# SCH_FMC-R2_MTOP_2026-02-22.net
KiCad netlist of a schematic drawn in EasyEDA
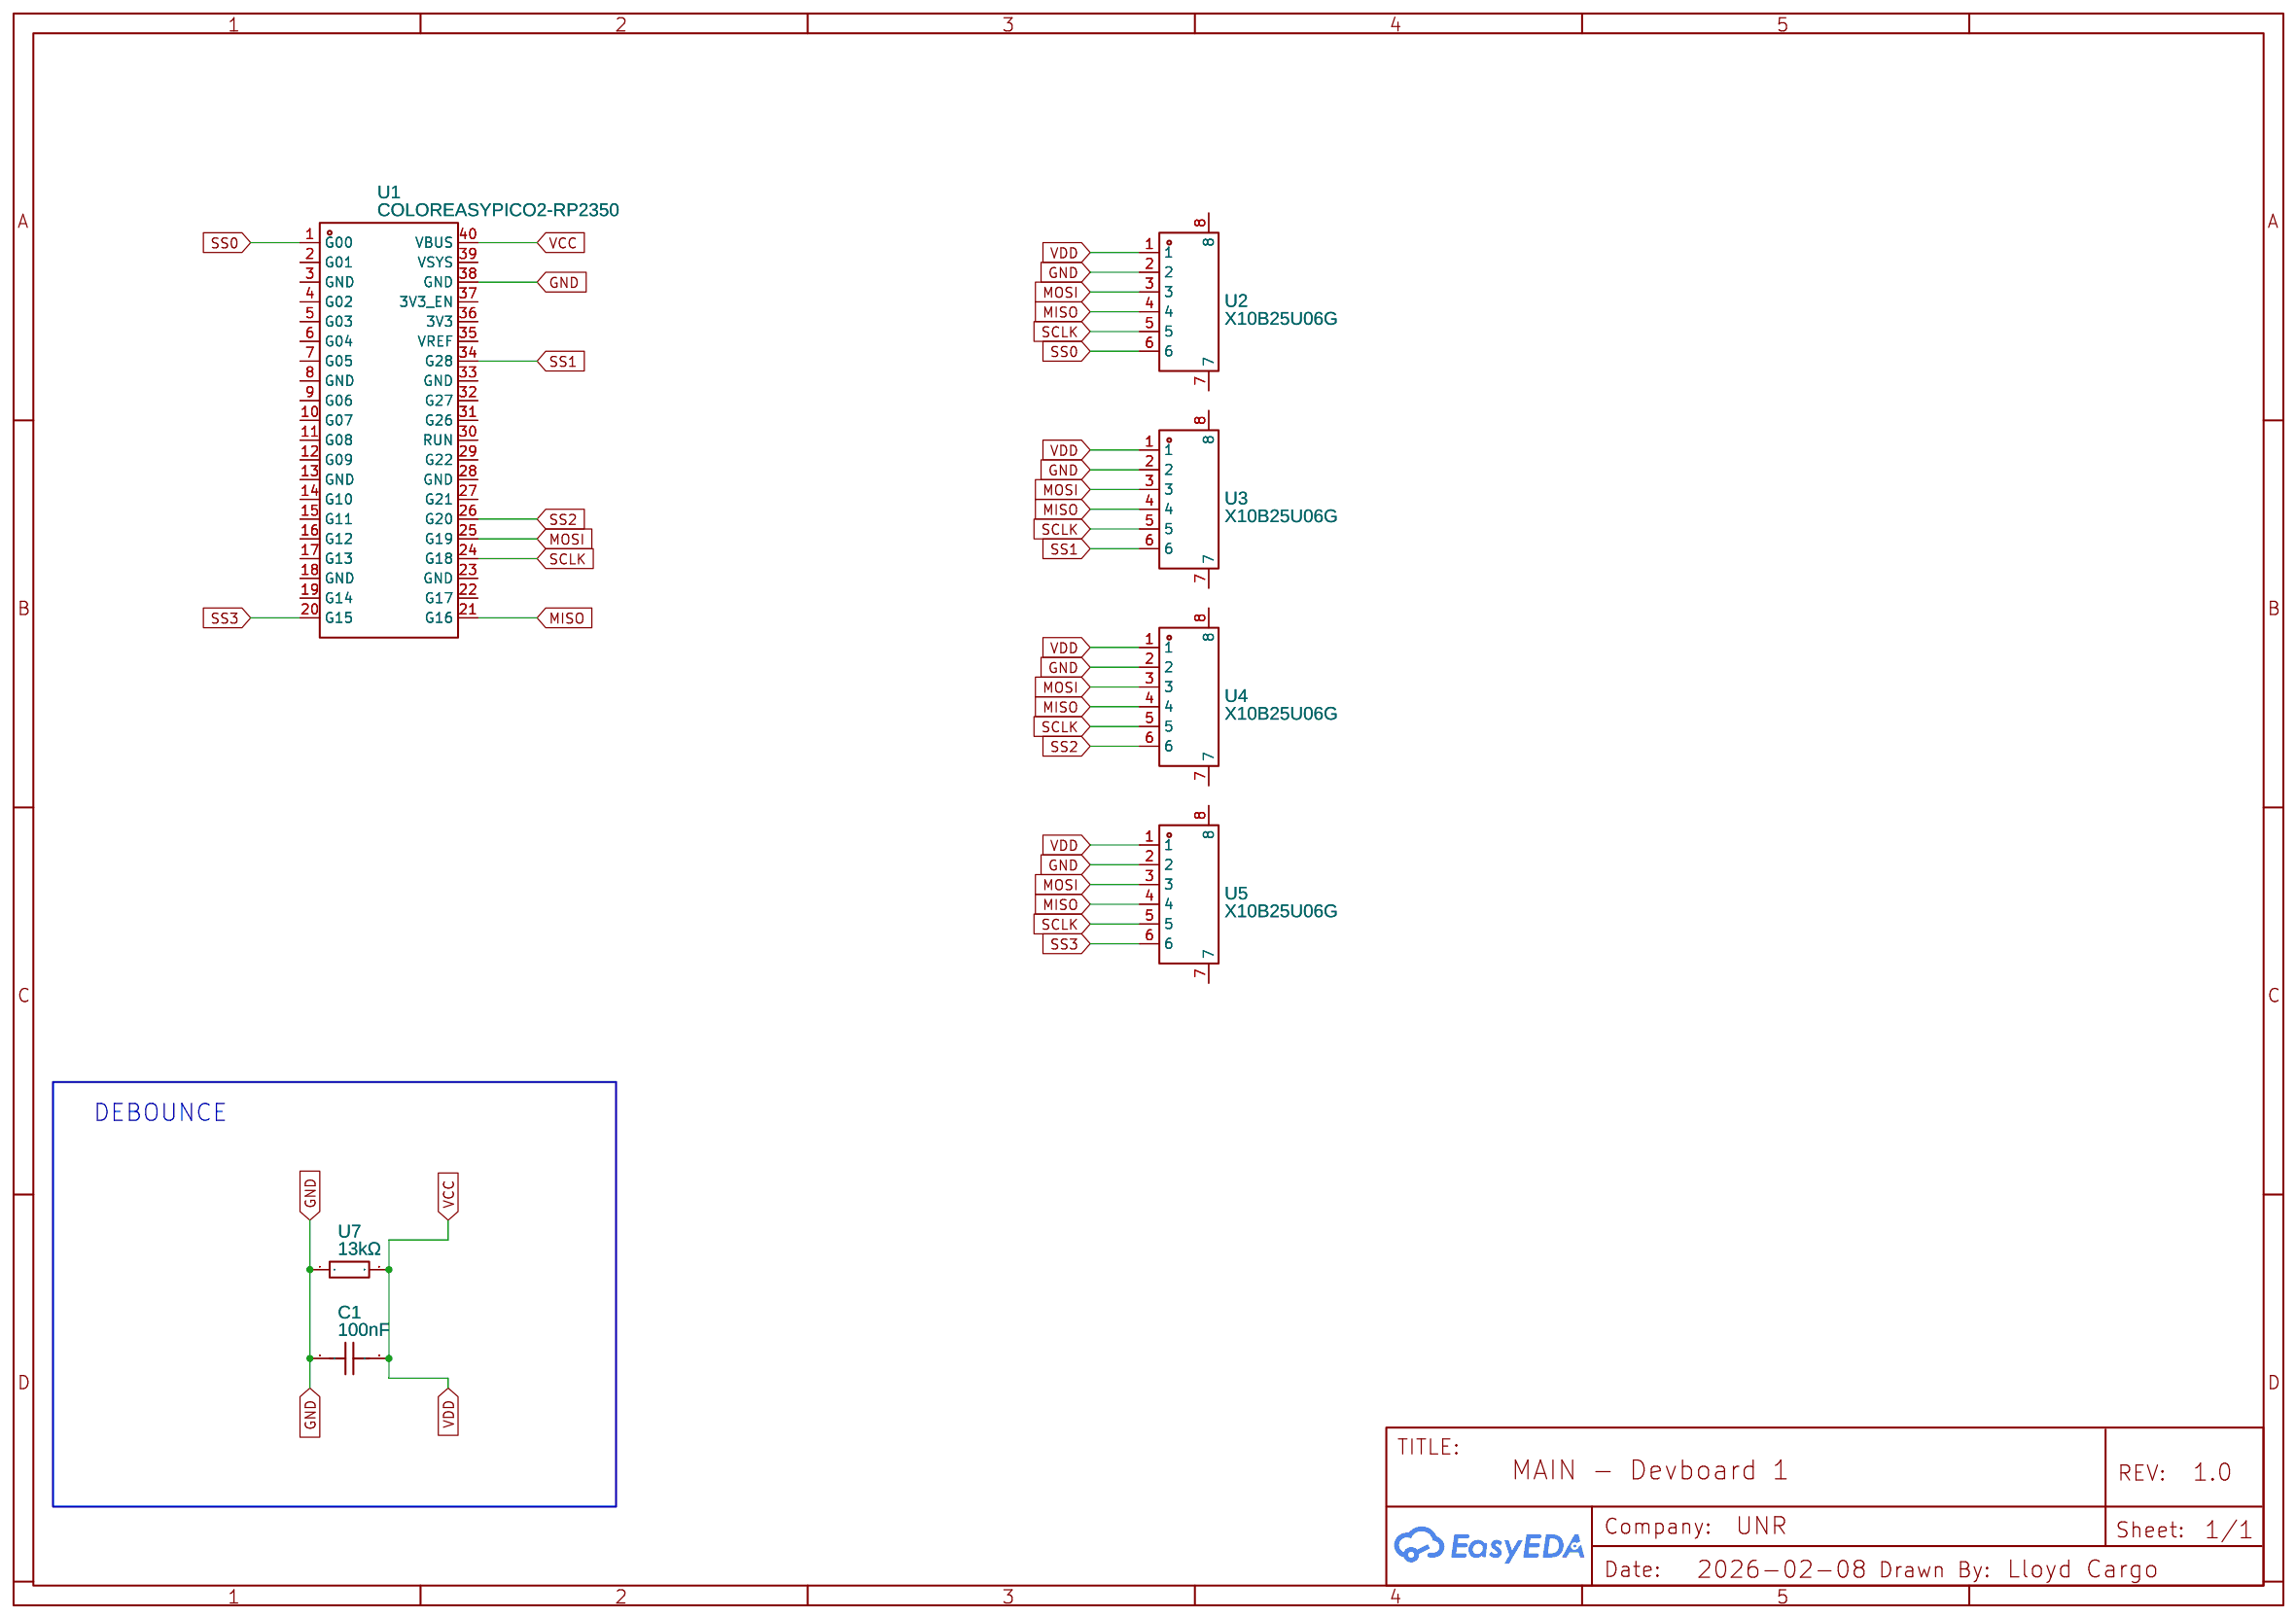
[diagram p0: MAIN]
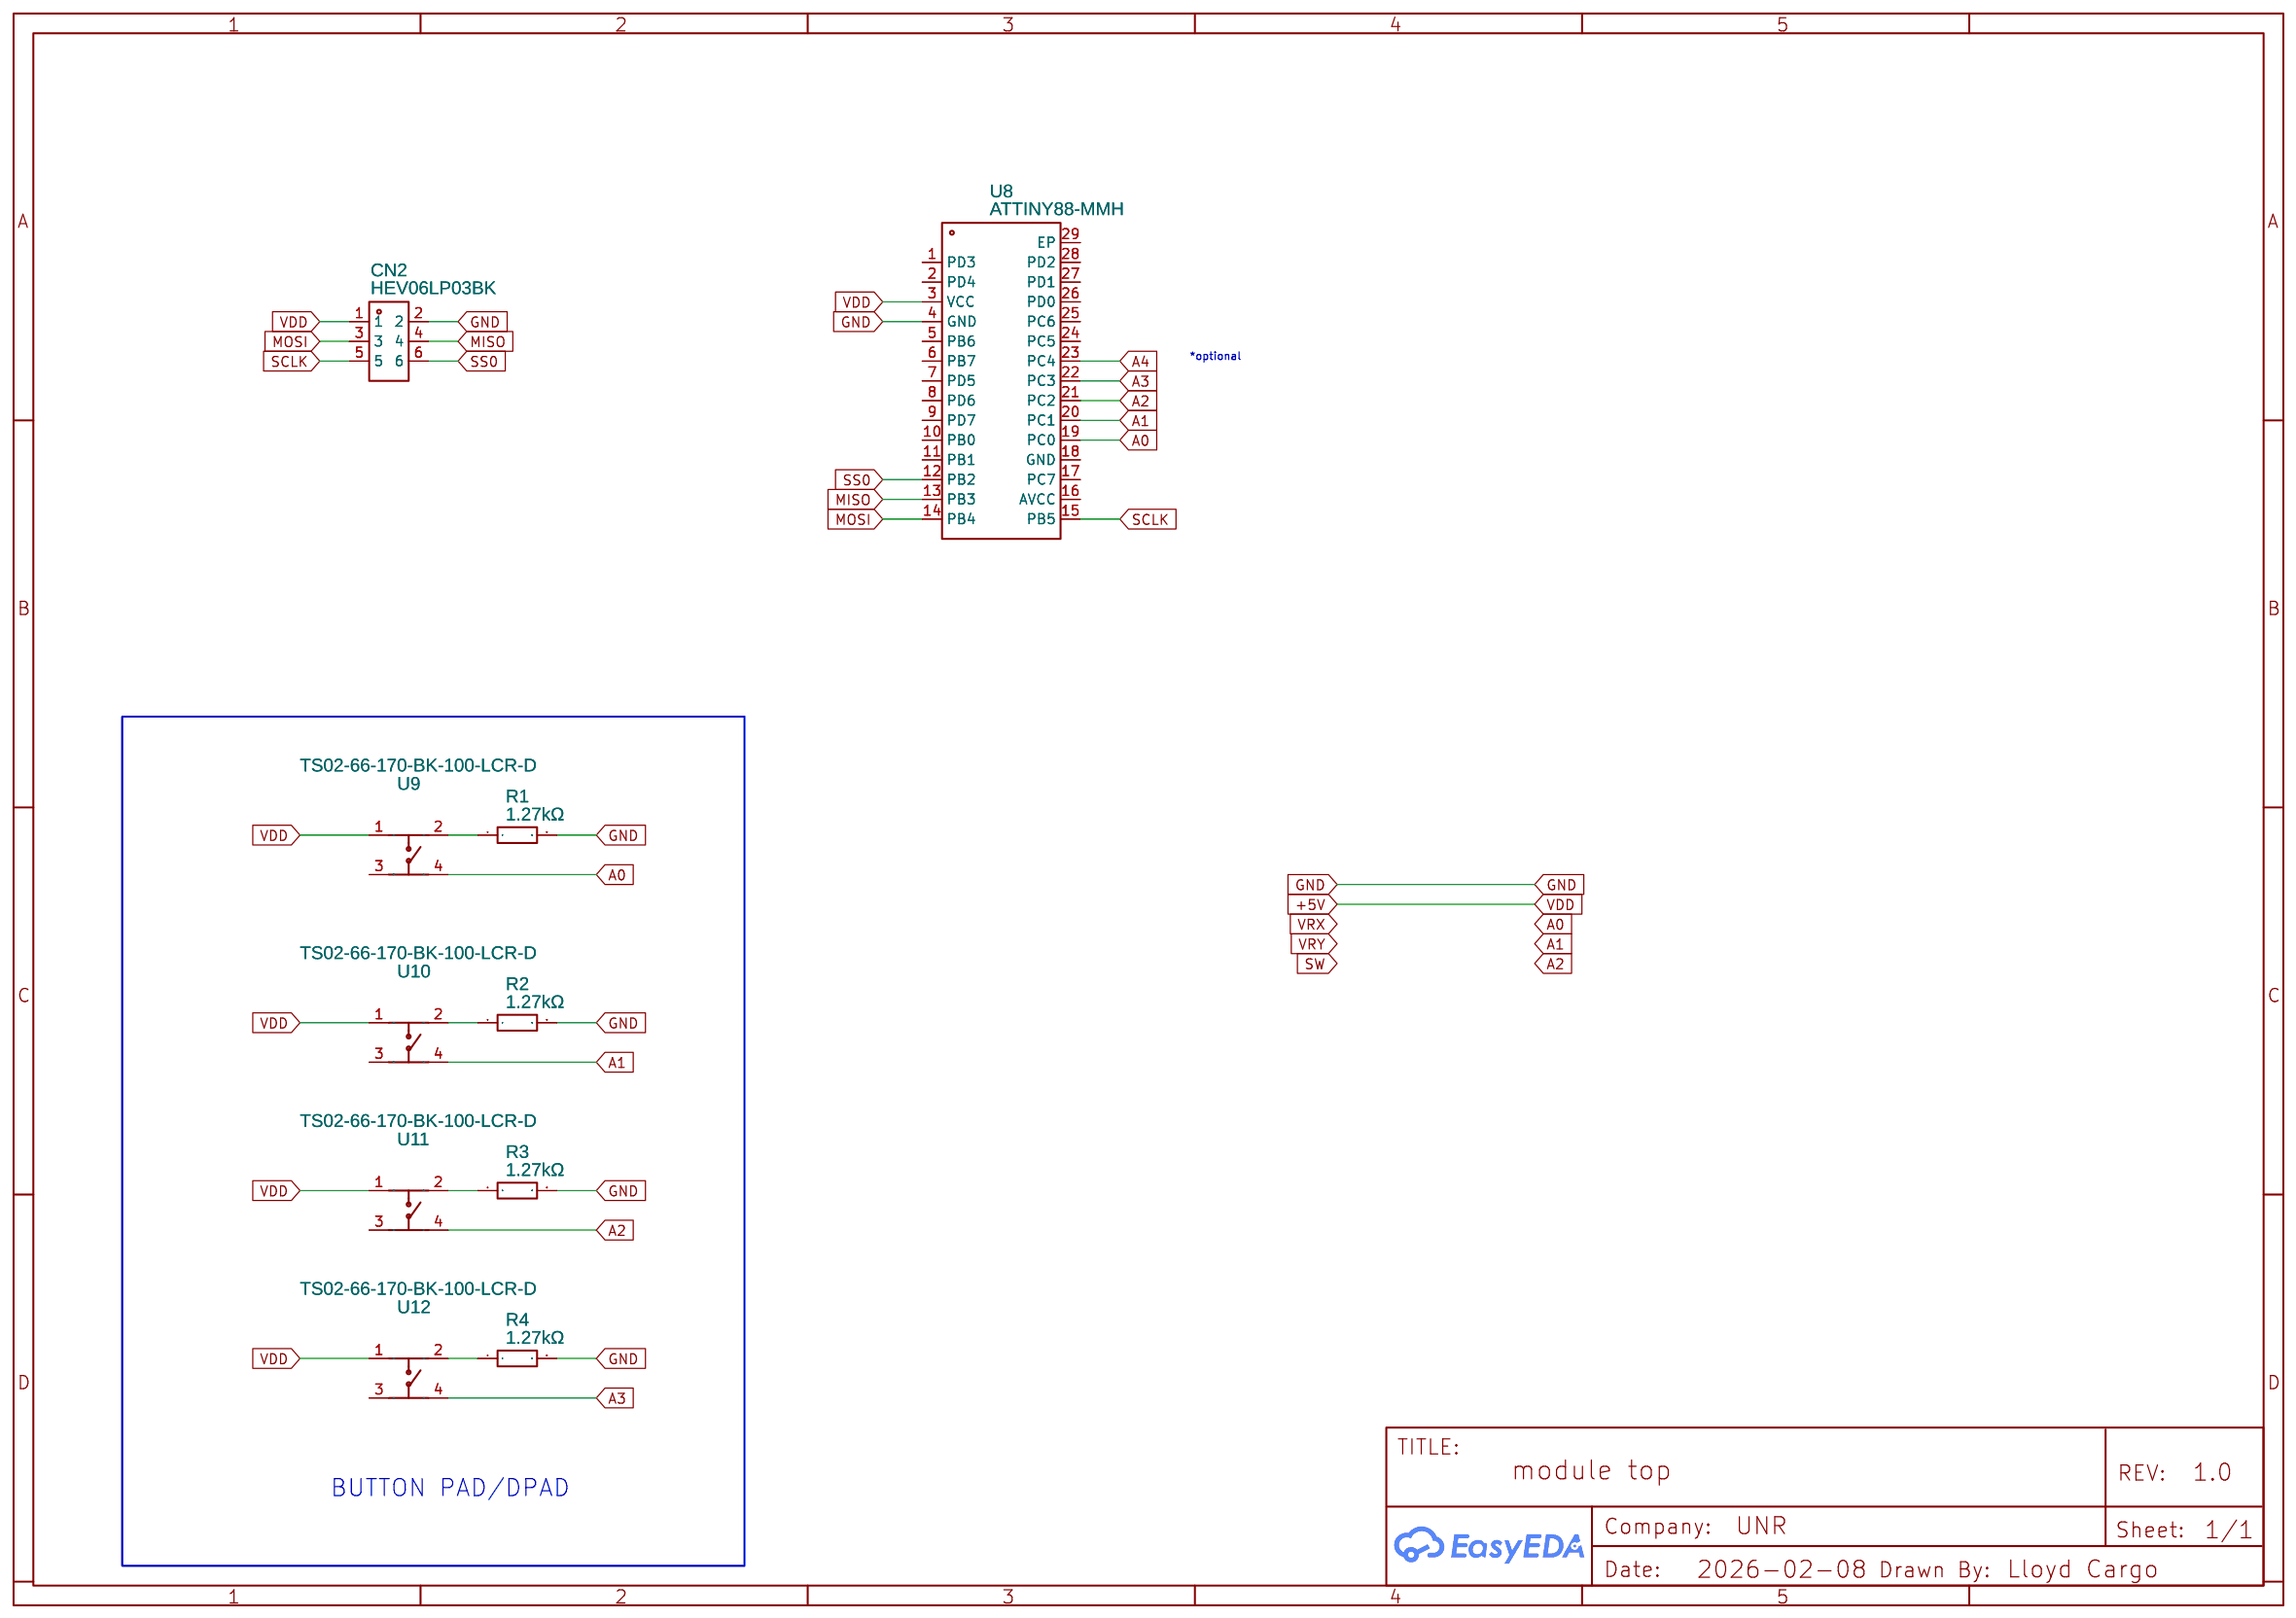
[diagram p1: module top]
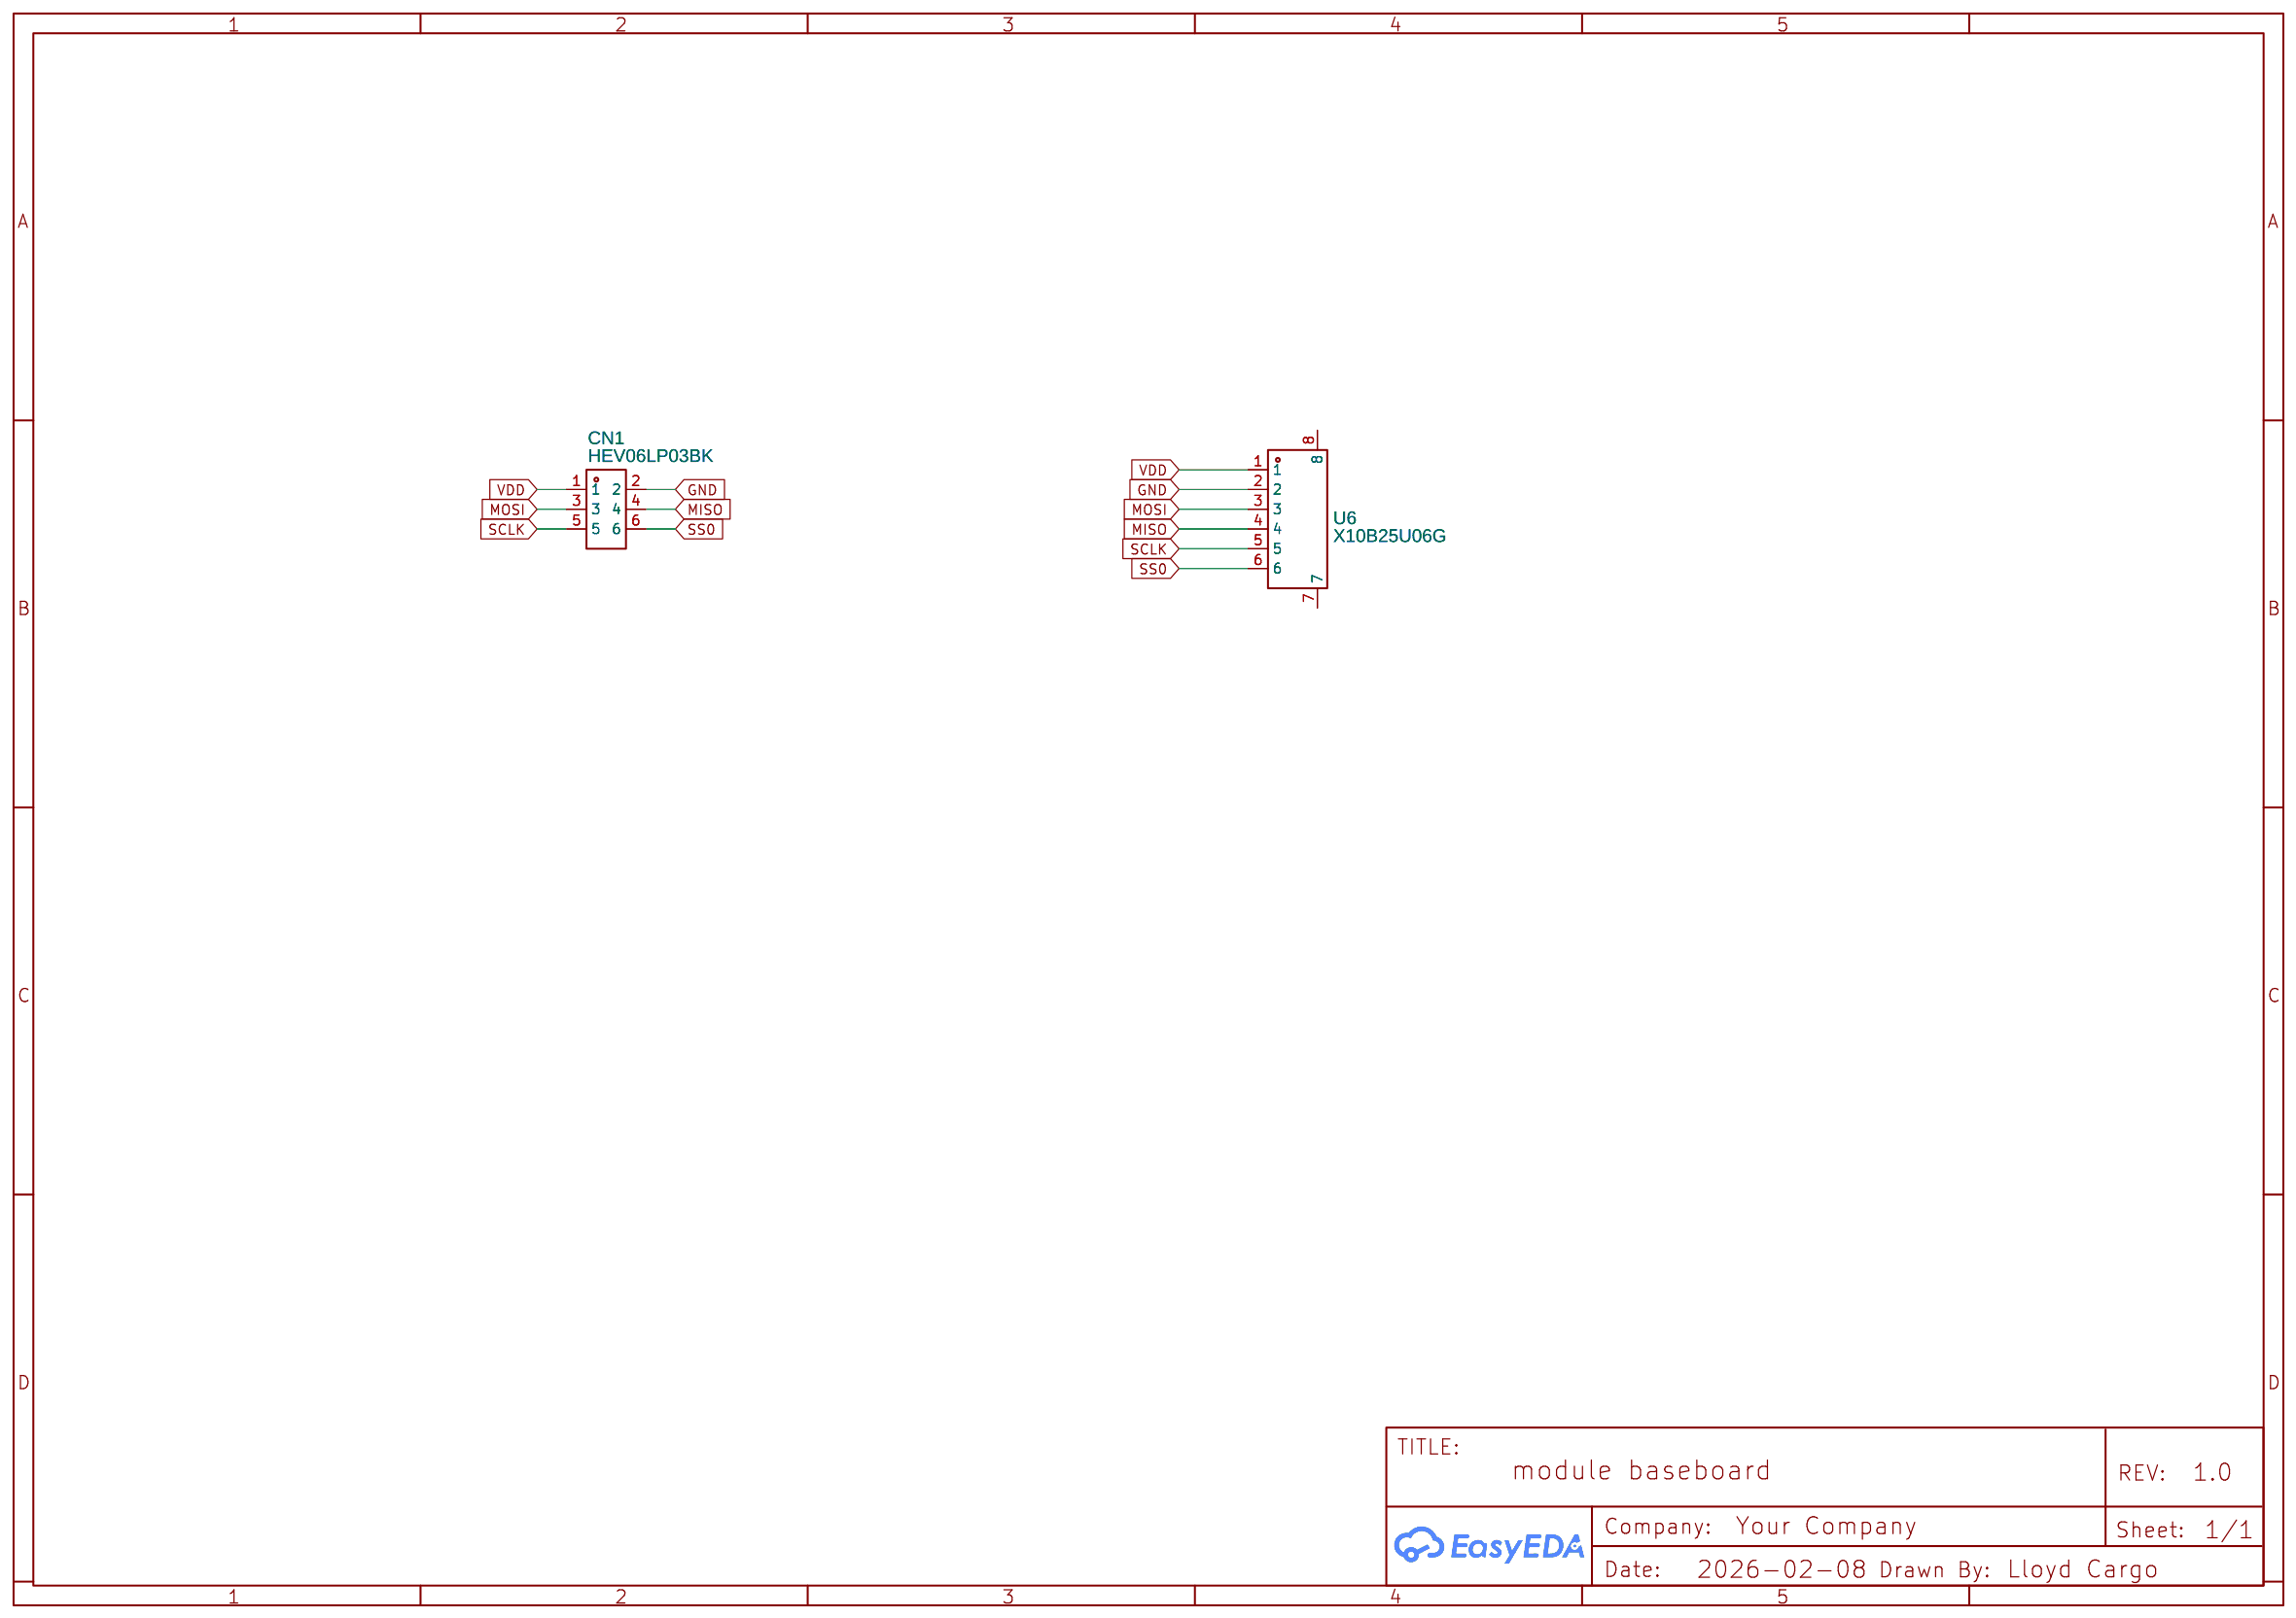
[diagram p2: module baseboard]

(export (version "E")
  (design (tool "Eeschema 10.0.6"))
  (components
    (comp (ref "C1")
      (value "100nF")
      (fields
        (field (name "Manufacturer Part") "GCG188R92A104KA03D")
        (field (name "Manufacturer") "muRata(村田)")
      )
      (libsource (lib "") (part "GCG188R92A104KA03D"))
    )
    (comp (ref "U1")
      (value "COLOREASYPICO2-RP2350")
      (fields
        (field (name "Manufacturer Part") "ColorEasyPico2-RP2350")
        (field (name "Manufacturer") "立创开发板")
      )
      (libsource (lib "") (part "COLOREASYPICO2-RP2350"))
    )
    (comp (ref "U2")
      (value "X10B25U06G")
      (fields (field (name "Manufacturer") "XKB Connection(中国星坤)"))
      (libsource (lib "") (part "X10B25U06G"))
    )
    (comp (ref "U3")
      (value "X10B25U06G")
      (fields (field (name "Manufacturer") "XKB Connection(中国星坤)"))
      (libsource (lib "") (part "X10B25U06G"))
    )
    (comp (ref "U4")
      (value "X10B25U06G")
      (fields (field (name "Manufacturer") "XKB Connection(中国星坤)"))
      (libsource (lib "") (part "X10B25U06G"))
    )
    (comp (ref "U5")
      (value "X10B25U06G")
      (fields (field (name "Manufacturer") "XKB Connection(中国星坤)"))
      (libsource (lib "") (part "X10B25U06G"))
    )
    (comp (ref "U7")
      (value "13kΩ")
      (fields (field (name "Manufacturer Part") "HPCR0805F13K0K9") (field (name "Manufacturer") "RESI(开步睿思)"))
      (libsource (lib "") (part "HPCR0805F13K0K9"))
    )
    (comp (ref "CN2")
      (value "HEV06LP03BK")
      (fields (field (name "Manufacturer") "WingTAT(格林柏)"))
      (libsource (lib "") (part "HEV06LP03BK"))
    )
    (comp (ref "R1")
      (value "1.27kΩ")
      (fields (field (name "Manufacturer Part") "RC0603FR-071K27L") (field (name "Manufacturer") "YAGEO(国巨)"))
      (libsource (lib "") (part "RC0603FR-071K27L"))
    )
    (comp (ref "R2")
      (value "1.27kΩ")
      (fields (field (name "Manufacturer Part") "RC0603FR-071K27L") (field (name "Manufacturer") "YAGEO(国巨)"))
      (libsource (lib "") (part "RC0603FR-071K27L"))
    )
    (comp (ref "R3")
      (value "1.27kΩ")
      (fields (field (name "Manufacturer Part") "RC0603FR-071K27L") (field (name "Manufacturer") "YAGEO(国巨)"))
      (libsource (lib "") (part "RC0603FR-071K27L"))
    )
    (comp (ref "R4")
      (value "1.27kΩ")
      (fields (field (name "Manufacturer Part") "RC0603FR-071K27L") (field (name "Manufacturer") "YAGEO(国巨)"))
      (libsource (lib "") (part "RC0603FR-071K27L"))
    )
    (comp (ref "U8")
      (value "ATTINY88-MMH")
      (fields (field (name "Manufacturer") "MICROCHIP(美国微芯)"))
      (libsource (lib "") (part "ATTINY88-MMH"))
    )
    (comp (ref "U9")
      (value "TS02-66-170-BK-100-LCR-D")
      (fields (field (name "Manufacturer") "CUI"))
      (libsource (lib "") (part "TS02-66-170-BK-100-LCR-D"))
    )
    (comp (ref "U10")
      (value "TS02-66-170-BK-100-LCR-D")
      (fields (field (name "Manufacturer") "CUI"))
      (libsource (lib "") (part "TS02-66-170-BK-100-LCR-D"))
    )
    (comp (ref "U11")
      (value "TS02-66-170-BK-100-LCR-D")
      (fields (field (name "Manufacturer") "CUI"))
      (libsource (lib "") (part "TS02-66-170-BK-100-LCR-D"))
    )
    (comp (ref "U12")
      (value "TS02-66-170-BK-100-LCR-D")
      (fields (field (name "Manufacturer") "CUI"))
      (libsource (lib "") (part "TS02-66-170-BK-100-LCR-D"))
    )
    (comp (ref "CN1")
      (value "HEV06LP03BK")
      (fields (field (name "Manufacturer") "WingTAT(格林柏)"))
      (libsource (lib "") (part "HEV06LP03BK"))
    )
    (comp (ref "U6")
      (value "X10B25U06G")
      (fields (field (name "Manufacturer") "XKB Connection(中国星坤)"))
      (libsource (lib "") (part "X10B25U06G"))
    )
  )
  (nets
    (net (code "1") (name "+5V") (class "Default")
      (node (ref "C1") (pin "2") (pinfunction "2_2") (pintype "unspecified"))
      (node (ref "CN1") (pin "1") (pinfunction "1_1") (pintype "unspecified"))
      (node (ref "CN2") (pin "1") (pinfunction "1_1") (pintype "unspecified"))
      (node (ref "U1") (pin "40") (pinfunction "VBUS_40") (pintype "unspecified"))
      (node (ref "U10") (pin "1") (pinfunction "1_1") (pintype "unspecified"))
      (node (ref "U11") (pin "1") (pinfunction "1_1") (pintype "unspecified"))
      (node (ref "U12") (pin "1") (pinfunction "1_1") (pintype "unspecified"))
      (node (ref "U2") (pin "1") (pinfunction "1_1") (pintype "unspecified"))
      (node (ref "U3") (pin "1") (pinfunction "1_1") (pintype "unspecified"))
      (node (ref "U4") (pin "1") (pinfunction "1_1") (pintype "unspecified"))
      (node (ref "U5") (pin "1") (pinfunction "1_1") (pintype "unspecified"))
      (node (ref "U6") (pin "1") (pinfunction "1_1") (pintype "unspecified"))
      (node (ref "U7") (pin "2") (pinfunction "2_2") (pintype "unspecified"))
      (node (ref "U8") (pin "3") (pinfunction "VCC_3") (pintype "unspecified"))
      (node (ref "U9") (pin "1") (pinfunction "1_1") (pintype "unspecified"))
    )
    (net (code "2") (name "A0") (class "Default")
      (node (ref "U8") (pin "19") (pinfunction "PC0_19") (pintype "unspecified"))
      (node (ref "U9") (pin "4") (pinfunction "4_4") (pintype "unspecified"))
    )
    (net (code "3") (name "A1") (class "Default")
      (node (ref "U10") (pin "4") (pinfunction "4_4") (pintype "unspecified"))
      (node (ref "U8") (pin "20") (pinfunction "PC1_20") (pintype "unspecified"))
    )
    (net (code "4") (name "A2") (class "Default")
      (node (ref "U11") (pin "4") (pinfunction "4_4") (pintype "unspecified"))
      (node (ref "U8") (pin "21") (pinfunction "PC2_21") (pintype "unspecified"))
    )
    (net (code "5") (name "A3") (class "Default")
      (node (ref "U12") (pin "4") (pinfunction "4_4") (pintype "unspecified"))
      (node (ref "U8") (pin "22") (pinfunction "PC3_22") (pintype "unspecified"))
    )
    (net (code "6") (name "A4") (class "Default")
      (node (ref "U8") (pin "23") (pinfunction "PC4_23") (pintype "unspecified"))
    )
    (net (code "7") (name "GND") (class "Default")
      (node (ref "C1") (pin "1") (pinfunction "1_1") (pintype "unspecified"))
      (node (ref "CN1") (pin "2") (pinfunction "2_2") (pintype "unspecified"))
      (node (ref "CN2") (pin "2") (pinfunction "2_2") (pintype "unspecified"))
      (node (ref "R1") (pin "2") (pinfunction "2_2") (pintype "unspecified"))
      (node (ref "R2") (pin "2") (pinfunction "2_2") (pintype "unspecified"))
      (node (ref "R3") (pin "2") (pinfunction "2_2") (pintype "unspecified"))
      (node (ref "R4") (pin "2") (pinfunction "2_2") (pintype "unspecified"))
      (node (ref "U1") (pin "38") (pinfunction "GND_38") (pintype "unspecified"))
      (node (ref "U2") (pin "2") (pinfunction "2_2") (pintype "unspecified"))
      (node (ref "U3") (pin "2") (pinfunction "2_2") (pintype "unspecified"))
      (node (ref "U4") (pin "2") (pinfunction "2_2") (pintype "unspecified"))
      (node (ref "U5") (pin "2") (pinfunction "2_2") (pintype "unspecified"))
      (node (ref "U6") (pin "2") (pinfunction "2_2") (pintype "unspecified"))
      (node (ref "U7") (pin "1") (pinfunction "1_1") (pintype "unspecified"))
      (node (ref "U8") (pin "4") (pinfunction "GND_4") (pintype "unspecified"))
    )
    (net (code "8") (name "MISO") (class "Default")
      (node (ref "CN1") (pin "4") (pinfunction "4_4") (pintype "unspecified"))
      (node (ref "CN2") (pin "4") (pinfunction "4_4") (pintype "unspecified"))
      (node (ref "U1") (pin "21") (pinfunction "G16_21") (pintype "unspecified"))
      (node (ref "U2") (pin "4") (pinfunction "4_4") (pintype "unspecified"))
      (node (ref "U3") (pin "4") (pinfunction "4_4") (pintype "unspecified"))
      (node (ref "U4") (pin "4") (pinfunction "4_4") (pintype "unspecified"))
      (node (ref "U5") (pin "4") (pinfunction "4_4") (pintype "unspecified"))
      (node (ref "U6") (pin "4") (pinfunction "4_4") (pintype "unspecified"))
      (node (ref "U8") (pin "13") (pinfunction "PB3_13") (pintype "unspecified"))
    )
    (net (code "9") (name "MOSI") (class "Default")
      (node (ref "CN1") (pin "3") (pinfunction "3_3") (pintype "unspecified"))
      (node (ref "CN2") (pin "3") (pinfunction "3_3") (pintype "unspecified"))
      (node (ref "U1") (pin "25") (pinfunction "G19_25") (pintype "unspecified"))
      (node (ref "U2") (pin "3") (pinfunction "3_3") (pintype "unspecified"))
      (node (ref "U3") (pin "3") (pinfunction "3_3") (pintype "unspecified"))
      (node (ref "U4") (pin "3") (pinfunction "3_3") (pintype "unspecified"))
      (node (ref "U5") (pin "3") (pinfunction "3_3") (pintype "unspecified"))
      (node (ref "U6") (pin "3") (pinfunction "3_3") (pintype "unspecified"))
      (node (ref "U8") (pin "14") (pinfunction "PB4_14") (pintype "unspecified"))
    )
    (net (code "10") (name "Net-(R1-Pad1)") (class "Default")
      (node (ref "R1") (pin "1") (pinfunction "1_1") (pintype "unspecified"))
      (node (ref "U9") (pin "2") (pinfunction "2_2") (pintype "unspecified"))
    )
    (net (code "11") (name "Net-(R2-Pad1)") (class "Default")
      (node (ref "R2") (pin "1") (pinfunction "1_1") (pintype "unspecified"))
      (node (ref "U10") (pin "2") (pinfunction "2_2") (pintype "unspecified"))
    )
    (net (code "12") (name "Net-(R3-Pad1)") (class "Default")
      (node (ref "R3") (pin "1") (pinfunction "1_1") (pintype "unspecified"))
      (node (ref "U11") (pin "2") (pinfunction "2_2") (pintype "unspecified"))
    )
    (net (code "13") (name "Net-(R4-Pad1)") (class "Default")
      (node (ref "R4") (pin "1") (pinfunction "1_1") (pintype "unspecified"))
      (node (ref "U12") (pin "2") (pinfunction "2_2") (pintype "unspecified"))
    )
    (net (code "14") (name "SCLK") (class "Default")
      (node (ref "CN1") (pin "5") (pinfunction "5_5") (pintype "unspecified"))
      (node (ref "CN2") (pin "5") (pinfunction "5_5") (pintype "unspecified"))
      (node (ref "U1") (pin "24") (pinfunction "G18_24") (pintype "unspecified"))
      (node (ref "U2") (pin "5") (pinfunction "5_5") (pintype "unspecified"))
      (node (ref "U3") (pin "5") (pinfunction "5_5") (pintype "unspecified"))
      (node (ref "U4") (pin "5") (pinfunction "5_5") (pintype "unspecified"))
      (node (ref "U5") (pin "5") (pinfunction "5_5") (pintype "unspecified"))
      (node (ref "U6") (pin "5") (pinfunction "5_5") (pintype "unspecified"))
      (node (ref "U8") (pin "15") (pinfunction "PB5_15") (pintype "unspecified"))
    )
    (net (code "15") (name "SS0") (class "Default")
      (node (ref "CN1") (pin "6") (pinfunction "6_6") (pintype "unspecified"))
      (node (ref "CN2") (pin "6") (pinfunction "6_6") (pintype "unspecified"))
      (node (ref "U1") (pin "1") (pinfunction "G00_1") (pintype "unspecified"))
      (node (ref "U2") (pin "6") (pinfunction "6_6") (pintype "unspecified"))
      (node (ref "U6") (pin "6") (pinfunction "6_6") (pintype "unspecified"))
      (node (ref "U8") (pin "12") (pinfunction "PB2_12") (pintype "unspecified"))
    )
    (net (code "16") (name "SS1") (class "Default")
      (node (ref "U1") (pin "34") (pinfunction "G28_34") (pintype "unspecified"))
      (node (ref "U3") (pin "6") (pinfunction "6_6") (pintype "unspecified"))
    )
    (net (code "17") (name "SS2") (class "Default")
      (node (ref "U1") (pin "26") (pinfunction "G20_26") (pintype "unspecified"))
      (node (ref "U4") (pin "6") (pinfunction "6_6") (pintype "unspecified"))
    )
    (net (code "18") (name "SS3") (class "Default")
      (node (ref "U1") (pin "20") (pinfunction "G15_20") (pintype "unspecified"))
      (node (ref "U5") (pin "6") (pinfunction "6_6") (pintype "unspecified"))
    )
    (net (code "22") (name "unconnected-(U1-3V3-Pad36)") (class "Default")
      (node (ref "U1") (pin "36") (pinfunction "3V3_36") (pintype "unspecified"))
    )
    (net (code "23") (name "unconnected-(U1-3V3_EN-Pad37)") (class "Default")
      (node (ref "U1") (pin "37") (pinfunction "3V3_EN_37") (pintype "unspecified"))
    )
    (net (code "24") (name "unconnected-(U1-G01-Pad2)") (class "Default")
      (node (ref "U1") (pin "2") (pinfunction "G01_2") (pintype "unspecified"))
    )
    (net (code "25") (name "unconnected-(U1-G02-Pad4)") (class "Default")
      (node (ref "U1") (pin "4") (pinfunction "G02_4") (pintype "unspecified"))
    )
    (net (code "26") (name "unconnected-(U1-G03-Pad5)") (class "Default")
      (node (ref "U1") (pin "5") (pinfunction "G03_5") (pintype "unspecified"))
    )
    (net (code "27") (name "unconnected-(U1-G04-Pad6)") (class "Default")
      (node (ref "U1") (pin "6") (pinfunction "G04_6") (pintype "unspecified"))
    )
    (net (code "28") (name "unconnected-(U1-G05-Pad7)") (class "Default")
      (node (ref "U1") (pin "7") (pinfunction "G05_7") (pintype "unspecified"))
    )
    (net (code "29") (name "unconnected-(U1-G06-Pad9)") (class "Default")
      (node (ref "U1") (pin "9") (pinfunction "G06_9") (pintype "unspecified"))
    )
    (net (code "30") (name "unconnected-(U1-G07-Pad10)") (class "Default")
      (node (ref "U1") (pin "10") (pinfunction "G07_10") (pintype "unspecified"))
    )
    (net (code "31") (name "unconnected-(U1-G08-Pad11)") (class "Default")
      (node (ref "U1") (pin "11") (pinfunction "G08_11") (pintype "unspecified"))
    )
    (net (code "32") (name "unconnected-(U1-G09-Pad12)") (class "Default")
      (node (ref "U1") (pin "12") (pinfunction "G09_12") (pintype "unspecified"))
    )
    (net (code "33") (name "unconnected-(U1-G10-Pad14)") (class "Default")
      (node (ref "U1") (pin "14") (pinfunction "G10_14") (pintype "unspecified"))
    )
    (net (code "34") (name "unconnected-(U1-G11-Pad15)") (class "Default")
      (node (ref "U1") (pin "15") (pinfunction "G11_15") (pintype "unspecified"))
    )
    (net (code "35") (name "unconnected-(U1-G12-Pad16)") (class "Default")
      (node (ref "U1") (pin "16") (pinfunction "G12_16") (pintype "unspecified"))
    )
    (net (code "36") (name "unconnected-(U1-G13-Pad17)") (class "Default")
      (node (ref "U1") (pin "17") (pinfunction "G13_17") (pintype "unspecified"))
    )
    (net (code "37") (name "unconnected-(U1-G14-Pad19)") (class "Default")
      (node (ref "U1") (pin "19") (pinfunction "G14_19") (pintype "unspecified"))
    )
    (net (code "38") (name "unconnected-(U1-G17-Pad22)") (class "Default")
      (node (ref "U1") (pin "22") (pinfunction "G17_22") (pintype "unspecified"))
    )
    (net (code "39") (name "unconnected-(U1-G21-Pad27)") (class "Default")
      (node (ref "U1") (pin "27") (pinfunction "G21_27") (pintype "unspecified"))
    )
    (net (code "40") (name "unconnected-(U1-G22-Pad29)") (class "Default")
      (node (ref "U1") (pin "29") (pinfunction "G22_29") (pintype "unspecified"))
    )
    (net (code "41") (name "unconnected-(U1-G26-Pad31)") (class "Default")
      (node (ref "U1") (pin "31") (pinfunction "G26_31") (pintype "unspecified"))
    )
    (net (code "42") (name "unconnected-(U1-G27-Pad32)") (class "Default")
      (node (ref "U1") (pin "32") (pinfunction "G27_32") (pintype "unspecified"))
    )
    (net (code "43") (name "unconnected-(U1-GND-Pad3)") (class "Default")
      (node (ref "U1") (pin "3") (pinfunction "GND_3") (pintype "unspecified"))
    )
    (net (code "44") (name "unconnected-(U1-GND-Pad8)") (class "Default")
      (node (ref "U1") (pin "8") (pinfunction "GND_8") (pintype "unspecified"))
    )
    (net (code "45") (name "unconnected-(U1-GND-Pad13)") (class "Default")
      (node (ref "U1") (pin "13") (pinfunction "GND_13") (pintype "unspecified"))
    )
    (net (code "46") (name "unconnected-(U1-GND-Pad18)") (class "Default")
      (node (ref "U1") (pin "18") (pinfunction "GND_18") (pintype "unspecified"))
    )
    (net (code "47") (name "unconnected-(U1-GND-Pad23)") (class "Default")
      (node (ref "U1") (pin "23") (pinfunction "GND_23") (pintype "unspecified"))
    )
    (net (code "48") (name "unconnected-(U1-GND-Pad28)") (class "Default")
      (node (ref "U1") (pin "28") (pinfunction "GND_28") (pintype "unspecified"))
    )
    (net (code "49") (name "unconnected-(U1-GND-Pad33)") (class "Default")
      (node (ref "U1") (pin "33") (pinfunction "GND_33") (pintype "unspecified"))
    )
    (net (code "50") (name "unconnected-(U1-RUN-Pad30)") (class "Default")
      (node (ref "U1") (pin "30") (pinfunction "RUN_30") (pintype "unspecified"))
    )
    (net (code "51") (name "unconnected-(U1-VREF-Pad35)") (class "Default")
      (node (ref "U1") (pin "35") (pinfunction "VREF_35") (pintype "unspecified"))
    )
    (net (code "52") (name "unconnected-(U1-VSYS-Pad39)") (class "Default")
      (node (ref "U1") (pin "39") (pinfunction "VSYS_39") (pintype "unspecified"))
    )
    (net (code "53") (name "unconnected-(U2-Pad7)") (class "Default")
      (node (ref "U2") (pin "7") (pinfunction "7_7") (pintype "unspecified"))
    )
    (net (code "54") (name "unconnected-(U2-Pad8)") (class "Default")
      (node (ref "U2") (pin "8") (pinfunction "8_8") (pintype "unspecified"))
    )
    (net (code "55") (name "unconnected-(U3-Pad7)") (class "Default")
      (node (ref "U3") (pin "7") (pinfunction "7_7") (pintype "unspecified"))
    )
    (net (code "56") (name "unconnected-(U3-Pad8)") (class "Default")
      (node (ref "U3") (pin "8") (pinfunction "8_8") (pintype "unspecified"))
    )
    (net (code "57") (name "unconnected-(U4-Pad7)") (class "Default")
      (node (ref "U4") (pin "7") (pinfunction "7_7") (pintype "unspecified"))
    )
    (net (code "58") (name "unconnected-(U4-Pad8)") (class "Default")
      (node (ref "U4") (pin "8") (pinfunction "8_8") (pintype "unspecified"))
    )
    (net (code "59") (name "unconnected-(U5-Pad7)") (class "Default")
      (node (ref "U5") (pin "7") (pinfunction "7_7") (pintype "unspecified"))
    )
    (net (code "60") (name "unconnected-(U5-Pad8)") (class "Default")
      (node (ref "U5") (pin "8") (pinfunction "8_8") (pintype "unspecified"))
    )
    (net (code "61") (name "unconnected-(U6-Pad7)") (class "Default")
      (node (ref "U6") (pin "7") (pinfunction "7_7") (pintype "unspecified"))
    )
    (net (code "62") (name "unconnected-(U6-Pad8)") (class "Default")
      (node (ref "U6") (pin "8") (pinfunction "8_8") (pintype "unspecified"))
    )
    (net (code "63") (name "unconnected-(U8-AVCC-Pad16)") (class "Default")
      (node (ref "U8") (pin "16") (pinfunction "AVCC_16") (pintype "unspecified"))
    )
    (net (code "64") (name "unconnected-(U8-EP-Pad29)") (class "Default")
      (node (ref "U8") (pin "29") (pinfunction "EP_29") (pintype "unspecified"))
    )
    (net (code "65") (name "unconnected-(U8-GND-Pad18)") (class "Default")
      (node (ref "U8") (pin "18") (pinfunction "GND_18") (pintype "unspecified"))
    )
    (net (code "66") (name "unconnected-(U8-PB0-Pad10)") (class "Default")
      (node (ref "U8") (pin "10") (pinfunction "PB0_10") (pintype "unspecified"))
    )
    (net (code "67") (name "unconnected-(U8-PB1-Pad11)") (class "Default")
      (node (ref "U8") (pin "11") (pinfunction "PB1_11") (pintype "unspecified"))
    )
    (net (code "68") (name "unconnected-(U8-PB6-Pad5)") (class "Default")
      (node (ref "U8") (pin "5") (pinfunction "PB6_5") (pintype "unspecified"))
    )
    (net (code "69") (name "unconnected-(U8-PB7-Pad6)") (class "Default")
      (node (ref "U8") (pin "6") (pinfunction "PB7_6") (pintype "unspecified"))
    )
    (net (code "70") (name "unconnected-(U8-PC5-Pad24)") (class "Default")
      (node (ref "U8") (pin "24") (pinfunction "PC5_24") (pintype "unspecified"))
    )
    (net (code "71") (name "unconnected-(U8-PC6-Pad25)") (class "Default")
      (node (ref "U8") (pin "25") (pinfunction "PC6_25") (pintype "unspecified"))
    )
    (net (code "72") (name "unconnected-(U8-PC7-Pad17)") (class "Default")
      (node (ref "U8") (pin "17") (pinfunction "PC7_17") (pintype "unspecified"))
    )
    (net (code "73") (name "unconnected-(U8-PD0-Pad26)") (class "Default")
      (node (ref "U8") (pin "26") (pinfunction "PD0_26") (pintype "unspecified"))
    )
    (net (code "74") (name "unconnected-(U8-PD1-Pad27)") (class "Default")
      (node (ref "U8") (pin "27") (pinfunction "PD1_27") (pintype "unspecified"))
    )
    (net (code "75") (name "unconnected-(U8-PD2-Pad28)") (class "Default")
      (node (ref "U8") (pin "28") (pinfunction "PD2_28") (pintype "unspecified"))
    )
    (net (code "76") (name "unconnected-(U8-PD3-Pad1)") (class "Default")
      (node (ref "U8") (pin "1") (pinfunction "PD3_1") (pintype "unspecified"))
    )
    (net (code "77") (name "unconnected-(U8-PD4-Pad2)") (class "Default")
      (node (ref "U8") (pin "2") (pinfunction "PD4_2") (pintype "unspecified"))
    )
    (net (code "78") (name "unconnected-(U8-PD5-Pad7)") (class "Default")
      (node (ref "U8") (pin "7") (pinfunction "PD5_7") (pintype "unspecified"))
    )
    (net (code "79") (name "unconnected-(U8-PD6-Pad8)") (class "Default")
      (node (ref "U8") (pin "8") (pinfunction "PD6_8") (pintype "unspecified"))
    )
    (net (code "80") (name "unconnected-(U8-PD7-Pad9)") (class "Default")
      (node (ref "U8") (pin "9") (pinfunction "PD7_9") (pintype "unspecified"))
    )
    (net (code "81") (name "unconnected-(U9-Pad3)") (class "Default")
      (node (ref "U9") (pin "3") (pinfunction "3_3") (pintype "unspecified"))
    )
    (net (code "82") (name "unconnected-(U10-Pad3)") (class "Default")
      (node (ref "U10") (pin "3") (pinfunction "3_3") (pintype "unspecified"))
    )
    (net (code "83") (name "unconnected-(U11-Pad3)") (class "Default")
      (node (ref "U11") (pin "3") (pinfunction "3_3") (pintype "unspecified"))
    )
    (net (code "84") (name "unconnected-(U12-Pad3)") (class "Default")
      (node (ref "U12") (pin "3") (pinfunction "3_3") (pintype "unspecified"))
    )
  )
)
